# Page-6.net
KiCad netlist of a schematic drawn in Altium Designer
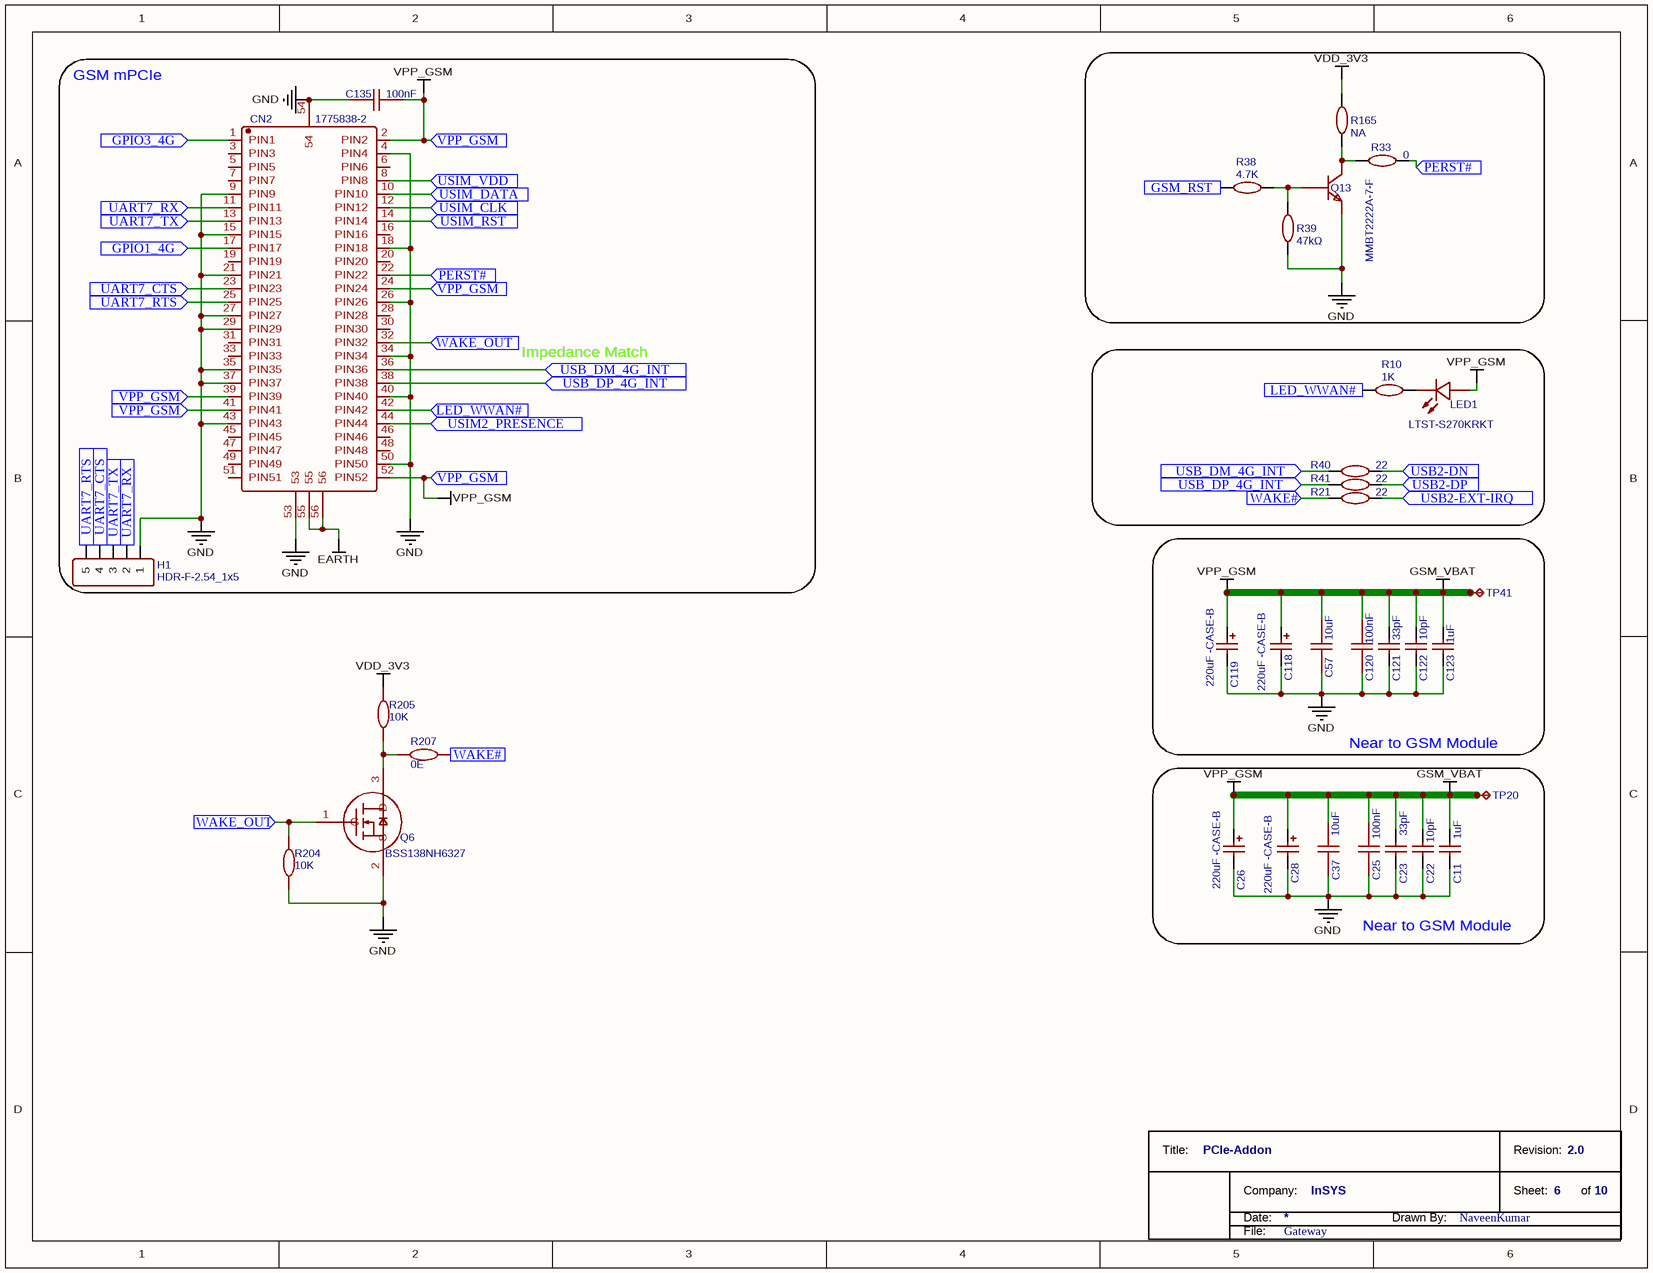
[diagram p0: Page-6.schdoc]

(export (version "E")
  (design (tool "Eeschema 10.0.6"))
  (components
    (comp (ref "*")
      (value "TitleBlock_1")
      (description "TitleBlock  No-2")
      (fields (field (name "DRAWN BY") "*"))
      (libsource (lib "GateWay_AllwinnerV2") (part "TitleBlock_1"))
    )
    (comp (ref "C11")
      (value "1uF")
      (footprint "GWAY_Capacitor_0603")
      (fields (field (name "MANUFACTURER PART") "CL10A105KO8NNNC") (field (name "MANUFACTURER") "SAMSUNG"))
      (libsource (lib "altium-import") (part "root_1_1uF_"))
    )
    (comp (ref "C22")
      (value "10pF")
      (footprint "GWAY_Capacitor_0603")
      (fields (field (name "MANUFACTURER PART") "CL10C100JB8NNNC") (field (name "MANUFACTURER") "SAMSUNG"))
      (libsource (lib "altium-import") (part "root_1_10pF_"))
    )
    (comp (ref "C23")
      (value "33pF")
      (footprint "GWAY_Capacitor_0603")
      (fields (field (name "MANUFACTURER PART") "CL10C330JB8NNNC") (field (name "MANUFACTURER") "SAMSUNG"))
      (libsource (lib "altium-import") (part "root_1_33pF_"))
    )
    (comp (ref "C25")
      (value "100nF")
      (footprint "GWAY_Capacitor_0603")
      (fields (field (name "MANUFACTURER") "SAMSUNG") (field (name "MANUFACTURER PART") "CL10B104KB8NNNC"))
      (libsource (lib "altium-import") (part "root_3_100nF_"))
    )
    (comp (ref "C26")
      (value "220uF -CASE-B")
      (footprint "GWAY_CASE-B")
      (fields (field (name "MANUFACTURER") "PANASONIC") (field (name "MANUFACTURER PART") "6TPE220MAZB"))
      (libsource (lib "altium-import") (part "root_3_220uF -CASE-B_"))
    )
    (comp (ref "C28")
      (value "220uF -CASE-B")
      (footprint "GWAY_CASE-B")
      (fields (field (name "MANUFACTURER") "PANASONIC") (field (name "MANUFACTURER PART") "6TPE220MAZB"))
      (libsource (lib "altium-import") (part "root_3_220uF -CASE-B_"))
    )
    (comp (ref "C37")
      (value "10uF")
      (footprint "GWAY_Capacitor_0805")
      (fields
        (field (name "MANUFACTURER") "SAMSUNG(三星)")
        (field (name "MANUFACTURER PART") "CL21B106KOQNNNE")
      )
      (libsource (lib "altium-import") (part "root_1_10uF_"))
    )
    (comp (ref "C57")
      (value "10uF")
      (footprint "GWAY_Capacitor_0603")
      (fields
        (field (name "MANUFACTURER") "SAMSUNG(三星)")
        (field (name "MANUFACTURER PART") "CL21B106KOQNNNE")
      )
      (libsource (lib "altium-import") (part "root_1_10uF_"))
    )
    (comp (ref "C118")
      (value "220uF -CASE-B")
      (footprint "GWAY_CASE-B")
      (fields (field (name "MANUFACTURER") "PANASONIC") (field (name "MANUFACTURER PART") "6TPE220MAZB"))
      (libsource (lib "altium-import") (part "root_3_220uF -CASE-B_"))
    )
    (comp (ref "C119")
      (value "220uF -CASE-B")
      (footprint "GWAY_CASE-B")
      (fields (field (name "MANUFACTURER") "PANASONIC") (field (name "MANUFACTURER PART") "6TPE220MAZB"))
      (libsource (lib "altium-import") (part "root_3_220uF -CASE-B_"))
    )
    (comp (ref "C120")
      (value "100nF")
      (footprint "GWAY_Capacitor_0603")
      (fields (field (name "MANUFACTURER") "SAMSUNG") (field (name "MANUFACTURER PART") "CL10B104KB8NNNC"))
      (libsource (lib "altium-import") (part "root_3_100nF_"))
    )
    (comp (ref "C121")
      (value "33pF")
      (footprint "GWAY_Capacitor_0603")
      (fields (field (name "MANUFACTURER PART") "CL10C330JB8NNNC") (field (name "MANUFACTURER") "SAMSUNG"))
      (libsource (lib "altium-import") (part "root_1_33pF_"))
    )
    (comp (ref "C122")
      (value "10pF")
      (footprint "GWAY_Capacitor_0603")
      (fields (field (name "MANUFACTURER PART") "CL10C100JB8NNNC") (field (name "MANUFACTURER") "SAMSUNG"))
      (libsource (lib "altium-import") (part "root_1_10pF_"))
    )
    (comp (ref "C123")
      (value "1uF")
      (footprint "GWAY_Capacitor_0603")
      (fields (field (name "MANUFACTURER PART") "CL10A105KO8NNNC") (field (name "MANUFACTURER") "SAMSUNG"))
      (libsource (lib "altium-import") (part "root_1_1uF_"))
    )
    (comp (ref "C135")
      (value "100nF")
      (footprint "GWAY_Capacitor_0603")
      (fields (field (name "MANUFACTURER") "SAMSUNG") (field (name "MANUFACTURER PART") "CL10B104KB8NNNC"))
      (libsource (lib "altium-import") (part "root_0_100nF_"))
    )
    (comp (ref "CN2")
      (value "1775838-2")
      (footprint "GWAY_TE_1775838-2_Full_Card")
      (description "PCIE Mini Full Card")
      (fields (field (name "MANUFACTURER") "TE Connectivity") (field (name "CONTRIBUTOR") "LCSC"))
      (libsource (lib "GateWay_AllwinnerV2") (part "PCIE Mini Full Card"))
    )
    (comp (ref "H1")
      (value "HDR-F-2.54_1x5")
      (footprint "GWAY_5way_HEADER_CONN")
      (fields (field (name "CONTRIBUTOR") "LCEDA_Lib"))
      (libsource (lib "altium-import") (part "root_3_HDR-F-2.54_1x5_"))
    )
    (comp (ref "LED1")
      (value "LTST-S270KRKT")
      (footprint "GWAY_Led_WHITE_0603")
      (fields
        (field (name "MANUFACTURER") "LITEON")
        (field (name "MANUFACTURER PART") "LTW-C193TS5")
        (field (name "CONTRIBUTOR") "LCSC")
      )
      (libsource (lib "altium-import") (part "root_0_LTST-S270KRKT_"))
    )
    (comp (ref "Q6")
      (value "BSS138NH6327")
      (footprint "GWAY_SOT23-3PIN")
      (fields (field (name "MANUFACTURER") "Infineon(英飞凌)") (field (name "CONTRIBUTOR") "LCSC"))
      (libsource (lib "GateWay_AllwinnerV2") (part "BSS138NH6327"))
    )
    (comp (ref "Q13")
      (value "MMBT2222A-7-F")
      (footprint "GWAY_SOT23-3PIN")
      (fields (field (name "MANUFACTURER") "DIODES(美台)") (field (name "CONTRIBUTOR") "LCSC"))
      (libsource (lib "altium-import") (part "root_0_MMBT2222A-7-F_"))
    )
    (comp (ref "R10")
      (value "1K")
      (footprint "GWAY_Resistor_0603")
      (fields (field (name "MANUFACTURER PART") "RC0603FR-071KL") (field (name "MANUFACTURER") "YAGEO"))
      (libsource (lib "altium-import") (part "root_0_1K_"))
    )
    (comp (ref "R21")
      (value "22")
      (footprint "GWAY_Resistor_0603")
      (fields (field (name "MANUFACTURER") "YAGEO") (field (name "MANUFACTURER PART") "RC0603FR-0722RL"))
      (libsource (lib "altium-import") (part "root_0_22_"))
    )
    (comp (ref "R33")
      (value "0")
      (footprint "GWAY_Resistor_0603")
      (fields (field (name "MANUFACTURER") "YAGEO") (field (name "MANUFACTURER PART") "RC0603FR-070RL"))
      (libsource (lib "altium-import") (part "root_0_0_"))
    )
    (comp (ref "R38")
      (value "4.7K")
      (footprint "GWAY_Resistor_0603")
      (fields (field (name "MANUFACTURER") "YAGEO") (field (name "MANUFACTURER PART") "RC0603FR-074K7L"))
      (libsource (lib "altium-import") (part "root_2_4.7K_"))
    )
    (comp (ref "R39")
      (value "47kΩ")
      (footprint "GWAY_Resistor_0603")
      (fields (field (name "MANUFACTURER") "YAGEO(国巨)"))
      (libsource (lib "altium-import") (part "root_1_47kΩ_"))
    )
    (comp (ref "R40")
      (value "22")
      (footprint "GWAY_Resistor_0603")
      (fields (field (name "MANUFACTURER") "YAGEO") (field (name "MANUFACTURER PART") "RC0603FR-0722RL"))
      (libsource (lib "altium-import") (part "root_0_22_"))
    )
    (comp (ref "R41")
      (value "22")
      (footprint "GWAY_Resistor_0603")
      (fields (field (name "MANUFACTURER") "YAGEO") (field (name "MANUFACTURER PART") "RC0603FR-0722RL"))
      (libsource (lib "altium-import") (part "root_0_22_"))
    )
    (comp (ref "R165")
      (value "NA")
      (footprint "GWAY_Resistor_0603")
      (fields (field (name "MANUFACTURER") "YAGEO") (field (name "MANUFACTURER PART") "RC0603FR-074K7L"))
      (libsource (lib "altium-import") (part "root_3_NA_"))
    )
    (comp (ref "R204")
      (value "10K")
      (footprint "GWAY_Resistor_0603")
      (fields
        (field (name "MANUFACTURER") "YAGEO")
        (field (name "MANUFACTURER PART") "RC0603FR-07100KL")
        (field (name "CONTRIBUTOR") "LCSC")
      )
      (libsource (lib "altium-import") (part "root_3_100K_"))
    )
    (comp (ref "R205")
      (value "10K")
      (footprint "GWAY_Resistor_0603")
      (fields
        (field (name "MANUFACTURER") "YAGEO")
        (field (name "MANUFACTURER PART") "RC0603FR-07100KL")
        (field (name "CONTRIBUTOR") "LCSC")
      )
      (libsource (lib "altium-import") (part "root_3_100K_"))
    )
    (comp (ref "R207")
      (value "0E")
      (footprint "GWAY_Resistor_0603")
      (fields
        (field (name "MANUFACTURER") "YAGEO")
        (field (name "MANUFACTURER PART") "RC0603FR-07100KL")
        (field (name "CONTRIBUTOR") "LCSC")
      )
      (libsource (lib "altium-import") (part "root_0_100K_"))
    )
    (comp (ref "TP20")
      (value "TP-052-TJ")
      (footprint "GWAY_TESTPOINT1")
      (fields (field (name "MANUFACTURER PART") "?"))
      (libsource (lib "altium-import") (part "root_3_TP-052-TJ_"))
    )
    (comp (ref "TP41")
      (value "TP-052-TJ")
      (footprint "GWAY_TESTPOINT1")
      (fields (field (name "MANUFACTURER PART") "?"))
      (libsource (lib "altium-import") (part "root_3_TP-052-TJ_"))
    )
  )
  (nets
    (net (code "1") (name "/GPIO1_4G") (class "Default")
      (node (ref "CN2") (pin "17") (pinfunction "PIN17_17") (pintype "passive"))
    )
    (net (code "2") (name "/GPIO3_4G") (class "Default")
      (node (ref "CN2") (pin "1") (pinfunction "PIN1_1") (pintype "passive"))
    )
    (net (code "3") (name "/GSM_RST") (class "Default")
      (node (ref "R38") (pin "2") (pinfunction "2_2") (pintype "passive"))
    )
    (net (code "4") (name "/LED_WWAN#") (class "Default")
      (node (ref "CN2") (pin "42") (pinfunction "PIN42_42") (pintype "passive"))
      (node (ref "R10") (pin "1") (pinfunction "1_1") (pintype "passive"))
    )
    (net (code "5") (name "/PERST#") (class "Default")
      (node (ref "CN2") (pin "22") (pinfunction "PIN22_22") (pintype "passive"))
      (node (ref "R33") (pin "2") (pinfunction "2_2") (pintype "passive"))
    )
    (net (code "6") (name "/UART7_CTS") (class "Default")
      (node (ref "CN2") (pin "23") (pinfunction "PIN23_23") (pintype "passive"))
      (node (ref "H1") (pin "4") (pinfunction "4_4") (pintype "passive"))
    )
    (net (code "7") (name "/UART7_RTS") (class "Default")
      (node (ref "CN2") (pin "25") (pinfunction "PIN25_25") (pintype "passive"))
      (node (ref "H1") (pin "5") (pinfunction "5_5") (pintype "passive"))
    )
    (net (code "8") (name "/UART7_RX") (class "Default")
      (node (ref "CN2") (pin "11") (pinfunction "PIN11_11") (pintype "passive"))
      (node (ref "H1") (pin "2") (pinfunction "2_2") (pintype "passive"))
    )
    (net (code "9") (name "/UART7_TX") (class "Default")
      (node (ref "CN2") (pin "13") (pinfunction "PIN13_13") (pintype "passive"))
      (node (ref "H1") (pin "3") (pinfunction "3_3") (pintype "passive"))
    )
    (net (code "10") (name "/USB2-DN") (class "Default")
      (node (ref "R40") (pin "2") (pinfunction "2_2") (pintype "passive"))
    )
    (net (code "11") (name "/USB2-DP") (class "Default")
      (node (ref "R41") (pin "2") (pinfunction "2_2") (pintype "passive"))
    )
    (net (code "12") (name "/USB2-EXT-IRQ") (class "Default")
      (node (ref "R21") (pin "2") (pinfunction "2_2") (pintype "passive"))
    )
    (net (code "13") (name "/USB_DM_4G_INT") (class "Default")
      (node (ref "CN2") (pin "36") (pinfunction "PIN36_36") (pintype "passive"))
      (node (ref "R40") (pin "1") (pinfunction "1_1") (pintype "passive"))
    )
    (net (code "14") (name "/USB_DP_4G_INT") (class "Default")
      (node (ref "CN2") (pin "38") (pinfunction "PIN38_38") (pintype "passive"))
      (node (ref "R41") (pin "1") (pinfunction "1_1") (pintype "passive"))
    )
    (net (code "15") (name "/USIM2_PRESENCE") (class "Default")
      (node (ref "CN2") (pin "44") (pinfunction "PIN44_44") (pintype "passive"))
    )
    (net (code "16") (name "/USIM_CLK") (class "Default")
      (node (ref "CN2") (pin "12") (pinfunction "PIN12_12") (pintype "passive"))
    )
    (net (code "17") (name "/USIM_DATA") (class "Default")
      (node (ref "CN2") (pin "10") (pinfunction "PIN10_10") (pintype "passive"))
    )
    (net (code "18") (name "/USIM_RST") (class "Default")
      (node (ref "CN2") (pin "14") (pinfunction "PIN14_14") (pintype "passive"))
    )
    (net (code "19") (name "/USIM_VDD") (class "Default")
      (node (ref "CN2") (pin "8") (pinfunction "PIN8_8") (pintype "passive"))
    )
    (net (code "20") (name "/WAKE#") (class "Default")
      (node (ref "R207") (pin "2") (pinfunction "2_2") (pintype "passive"))
      (node (ref "R21") (pin "1") (pinfunction "1_1") (pintype "passive"))
    )
    (net (code "21") (name "/WAKE_OUT") (class "Default")
      (node (ref "CN2") (pin "32") (pinfunction "PIN32_32") (pintype "passive"))
      (node (ref "Q6") (pin "1") (pinfunction "G_1") (pintype "passive"))
      (node (ref "R204") (pin "1") (pinfunction "1_1") (pintype "passive"))
    )
    (net (code "22") (name "EARTH") (class "Default")
      (node (ref "CN2") (pin "55") (pinfunction "55_55") (pintype "passive"))
      (node (ref "CN2") (pin "56") (pinfunction "56_56") (pintype "passive"))
    )
    (net (code "23") (name "GND") (class "Default")
      (node (ref "C11") (pin "1") (pinfunction "1_1") (pintype "passive"))
      (node (ref "C118") (pin "2") (pinfunction "2_2") (pintype "passive"))
      (node (ref "C119") (pin "2") (pinfunction "2_2") (pintype "passive"))
      (node (ref "C120") (pin "2") (pinfunction "2_2") (pintype "passive"))
      (node (ref "C121") (pin "1") (pinfunction "1_1") (pintype "passive"))
      (node (ref "C122") (pin "1") (pinfunction "1_1") (pintype "passive"))
      (node (ref "C123") (pin "1") (pinfunction "1_1") (pintype "passive"))
      (node (ref "C135") (pin "1") (pinfunction "1_1") (pintype "passive"))
      (node (ref "C22") (pin "1") (pinfunction "1_1") (pintype "passive"))
      (node (ref "C23") (pin "1") (pinfunction "1_1") (pintype "passive"))
      (node (ref "C25") (pin "2") (pinfunction "2_2") (pintype "passive"))
      (node (ref "C26") (pin "2") (pinfunction "2_2") (pintype "passive"))
      (node (ref "C28") (pin "2") (pinfunction "2_2") (pintype "passive"))
      (node (ref "C37") (pin "1") (pinfunction "1_1") (pintype "passive"))
      (node (ref "C57") (pin "1") (pinfunction "1_1") (pintype "passive"))
      (node (ref "CN2") (pin "15") (pinfunction "PIN15_15") (pintype "passive"))
      (node (ref "CN2") (pin "18") (pinfunction "PIN18_18") (pintype "passive"))
      (node (ref "CN2") (pin "21") (pinfunction "PIN21_21") (pintype "passive"))
      (node (ref "CN2") (pin "26") (pinfunction "PIN26_26") (pintype "passive"))
      (node (ref "CN2") (pin "27") (pinfunction "PIN27_27") (pintype "passive"))
      (node (ref "CN2") (pin "29") (pinfunction "PIN29_29") (pintype "passive"))
      (node (ref "CN2") (pin "34") (pinfunction "PIN34_34") (pintype "passive"))
      (node (ref "CN2") (pin "35") (pinfunction "PIN35_35") (pintype "passive"))
      (node (ref "CN2") (pin "37") (pinfunction "PIN37_37") (pintype "passive"))
      (node (ref "CN2") (pin "4") (pinfunction "PIN4_4") (pintype "passive"))
      (node (ref "CN2") (pin "40") (pinfunction "PIN40_40") (pintype "passive"))
      (node (ref "CN2") (pin "43") (pinfunction "PIN43_43") (pintype "passive"))
      (node (ref "CN2") (pin "50") (pinfunction "PIN50_50") (pintype "passive"))
      (node (ref "CN2") (pin "53") (pinfunction "53_53") (pintype "passive"))
      (node (ref "CN2") (pin "54") (pinfunction "54_54") (pintype "passive"))
      (node (ref "CN2") (pin "9") (pinfunction "PIN9_9") (pintype "passive"))
      (node (ref "H1") (pin "1") (pinfunction "1_1") (pintype "passive"))
      (node (ref "Q13") (pin "2") (pinfunction "E_2") (pintype "passive"))
      (node (ref "Q6") (pin "2") (pinfunction "S_2") (pintype "passive"))
      (node (ref "R204") (pin "2") (pinfunction "2_2") (pintype "passive"))
      (node (ref "R39") (pin "1") (pinfunction "1_1") (pintype "passive"))
    )
    (net (code "24") (name "GSM_VBAT") (class "Default")
      (node (ref "C11") (pin "2") (pinfunction "2_2") (pintype "passive"))
      (node (ref "C118") (pin "1") (pinfunction "1_1") (pintype "passive"))
      (node (ref "C119") (pin "1") (pinfunction "1_1") (pintype "passive"))
      (node (ref "C120") (pin "1") (pinfunction "1_1") (pintype "passive"))
      (node (ref "C121") (pin "2") (pinfunction "2_2") (pintype "passive"))
      (node (ref "C122") (pin "2") (pinfunction "2_2") (pintype "passive"))
      (node (ref "C123") (pin "2") (pinfunction "2_2") (pintype "passive"))
      (node (ref "C135") (pin "2") (pinfunction "2_2") (pintype "passive"))
      (node (ref "C22") (pin "2") (pinfunction "2_2") (pintype "passive"))
      (node (ref "C23") (pin "2") (pinfunction "2_2") (pintype "passive"))
      (node (ref "C25") (pin "1") (pinfunction "1_1") (pintype "passive"))
      (node (ref "C26") (pin "1") (pinfunction "1_1") (pintype "passive"))
      (node (ref "C28") (pin "1") (pinfunction "1_1") (pintype "passive"))
      (node (ref "C37") (pin "2") (pinfunction "2_2") (pintype "passive"))
      (node (ref "C57") (pin "2") (pinfunction "2_2") (pintype "passive"))
      (node (ref "CN2") (pin "2") (pinfunction "PIN2_2") (pintype "passive"))
      (node (ref "CN2") (pin "24") (pinfunction "PIN24_24") (pintype "passive"))
      (node (ref "CN2") (pin "39") (pinfunction "PIN39_39") (pintype "passive"))
      (node (ref "CN2") (pin "41") (pinfunction "PIN41_41") (pintype "passive"))
      (node (ref "CN2") (pin "52") (pinfunction "PIN52_52") (pintype "passive"))
      (node (ref "LED1") (pin "1") (pinfunction "A_1") (pintype "passive"))
      (node (ref "TP20") (pin "1") (pinfunction "1_1") (pintype "passive"))
      (node (ref "TP41") (pin "1") (pinfunction "1_1") (pintype "passive"))
    )
    (net (code "25") (name "Net-(LED1-K)") (class "Default")
      (node (ref "LED1") (pin "2") (pinfunction "K_2") (pintype "passive"))
      (node (ref "R10") (pin "2") (pinfunction "2_2") (pintype "passive"))
    )
    (net (code "26") (name "Net-(Q6-D)") (class "Default")
      (node (ref "Q6") (pin "3") (pinfunction "D_3") (pintype "passive"))
      (node (ref "R205") (pin "2") (pinfunction "2_2") (pintype "passive"))
      (node (ref "R207") (pin "1") (pinfunction "1_1") (pintype "passive"))
    )
    (net (code "27") (name "Net-(Q13-B)") (class "Default")
      (node (ref "Q13") (pin "1") (pinfunction "B_1") (pintype "passive"))
      (node (ref "R38") (pin "1") (pinfunction "1_1") (pintype "passive"))
      (node (ref "R39") (pin "2") (pinfunction "2_2") (pintype "passive"))
    )
    (net (code "28") (name "Net-(Q13-C)") (class "Default")
      (node (ref "Q13") (pin "3") (pinfunction "C_3") (pintype "passive"))
      (node (ref "R165") (pin "2") (pinfunction "2_2") (pintype "passive"))
      (node (ref "R33") (pin "1") (pinfunction "1_1") (pintype "passive"))
    )
    (net (code "29") (name "VDD_3V3") (class "Default")
      (node (ref "R165") (pin "1") (pinfunction "1_1") (pintype "passive"))
      (node (ref "R205") (pin "1") (pinfunction "1_1") (pintype "passive"))
    )
    (net (code "30") (name "unconnected-(CN2-PIN3-Pad3)") (class "Default")
      (node (ref "CN2") (pin "3") (pinfunction "PIN3_3") (pintype "passive"))
    )
    (net (code "31") (name "unconnected-(CN2-PIN5-Pad5)") (class "Default")
      (node (ref "CN2") (pin "5") (pinfunction "PIN5_5") (pintype "passive"))
    )
    (net (code "32") (name "unconnected-(CN2-PIN6-Pad6)") (class "Default")
      (node (ref "CN2") (pin "6") (pinfunction "PIN6_6") (pintype "passive"))
    )
    (net (code "33") (name "unconnected-(CN2-PIN7-Pad7)") (class "Default")
      (node (ref "CN2") (pin "7") (pinfunction "PIN7_7") (pintype "passive"))
    )
    (net (code "34") (name "unconnected-(CN2-PIN16-Pad16)") (class "Default")
      (node (ref "CN2") (pin "16") (pinfunction "PIN16_16") (pintype "passive"))
    )
    (net (code "35") (name "unconnected-(CN2-PIN19-Pad19)") (class "Default")
      (node (ref "CN2") (pin "19") (pinfunction "PIN19_19") (pintype "passive"))
    )
    (net (code "36") (name "unconnected-(CN2-PIN20-Pad20)") (class "Default")
      (node (ref "CN2") (pin "20") (pinfunction "PIN20_20") (pintype "passive"))
    )
    (net (code "37") (name "unconnected-(CN2-PIN28-Pad28)") (class "Default")
      (node (ref "CN2") (pin "28") (pinfunction "PIN28_28") (pintype "passive"))
    )
    (net (code "38") (name "unconnected-(CN2-PIN30-Pad30)") (class "Default")
      (node (ref "CN2") (pin "30") (pinfunction "PIN30_30") (pintype "passive"))
    )
    (net (code "39") (name "unconnected-(CN2-PIN31-Pad31)") (class "Default")
      (node (ref "CN2") (pin "31") (pinfunction "PIN31_31") (pintype "passive"))
    )
    (net (code "40") (name "unconnected-(CN2-PIN33-Pad33)") (class "Default")
      (node (ref "CN2") (pin "33") (pinfunction "PIN33_33") (pintype "passive"))
    )
    (net (code "41") (name "unconnected-(CN2-PIN45-Pad45)") (class "Default")
      (node (ref "CN2") (pin "45") (pinfunction "PIN45_45") (pintype "passive"))
    )
    (net (code "42") (name "unconnected-(CN2-PIN46-Pad46)") (class "Default")
      (node (ref "CN2") (pin "46") (pinfunction "PIN46_46") (pintype "passive"))
    )
    (net (code "43") (name "unconnected-(CN2-PIN47-Pad47)") (class "Default")
      (node (ref "CN2") (pin "47") (pinfunction "PIN47_47") (pintype "passive"))
    )
    (net (code "44") (name "unconnected-(CN2-PIN48-Pad48)") (class "Default")
      (node (ref "CN2") (pin "48") (pinfunction "PIN48_48") (pintype "passive"))
    )
    (net (code "45") (name "unconnected-(CN2-PIN49-Pad49)") (class "Default")
      (node (ref "CN2") (pin "49") (pinfunction "PIN49_49") (pintype "passive"))
    )
    (net (code "46") (name "unconnected-(CN2-PIN51-Pad51)") (class "Default")
      (node (ref "CN2") (pin "51") (pinfunction "PIN51_51") (pintype "passive"))
    )
  )
)
